# 06_-_CPU_-_HDMI_LVDS.net
KiCad netlist of a schematic drawn in Altium Designer
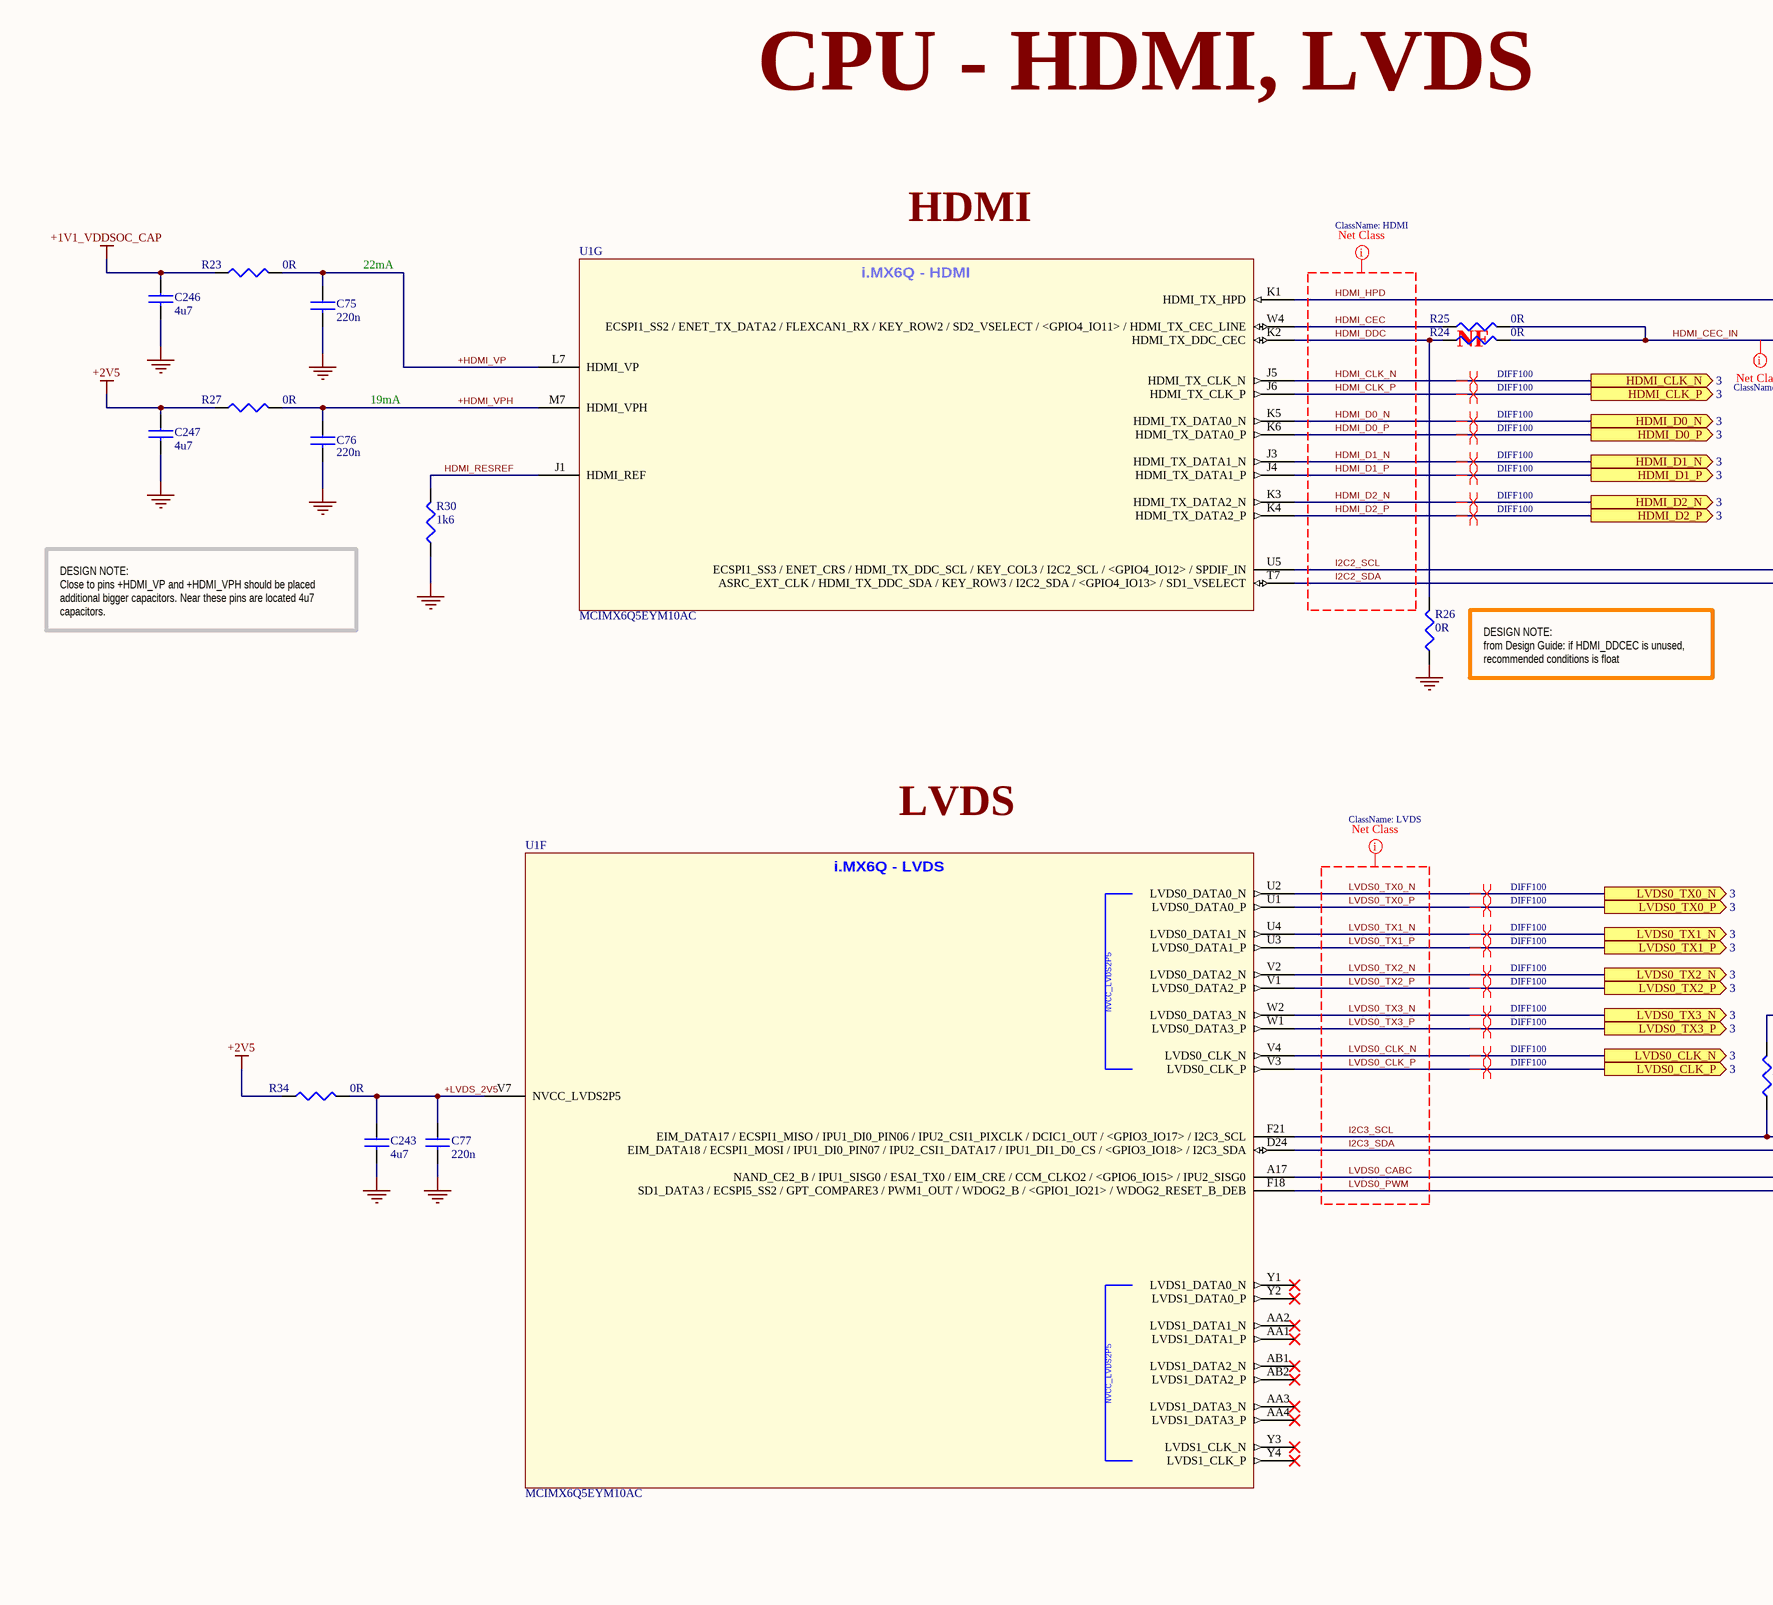
[diagram p0: [06] - CPU - HDMI, LVDS.SchDoc, left]
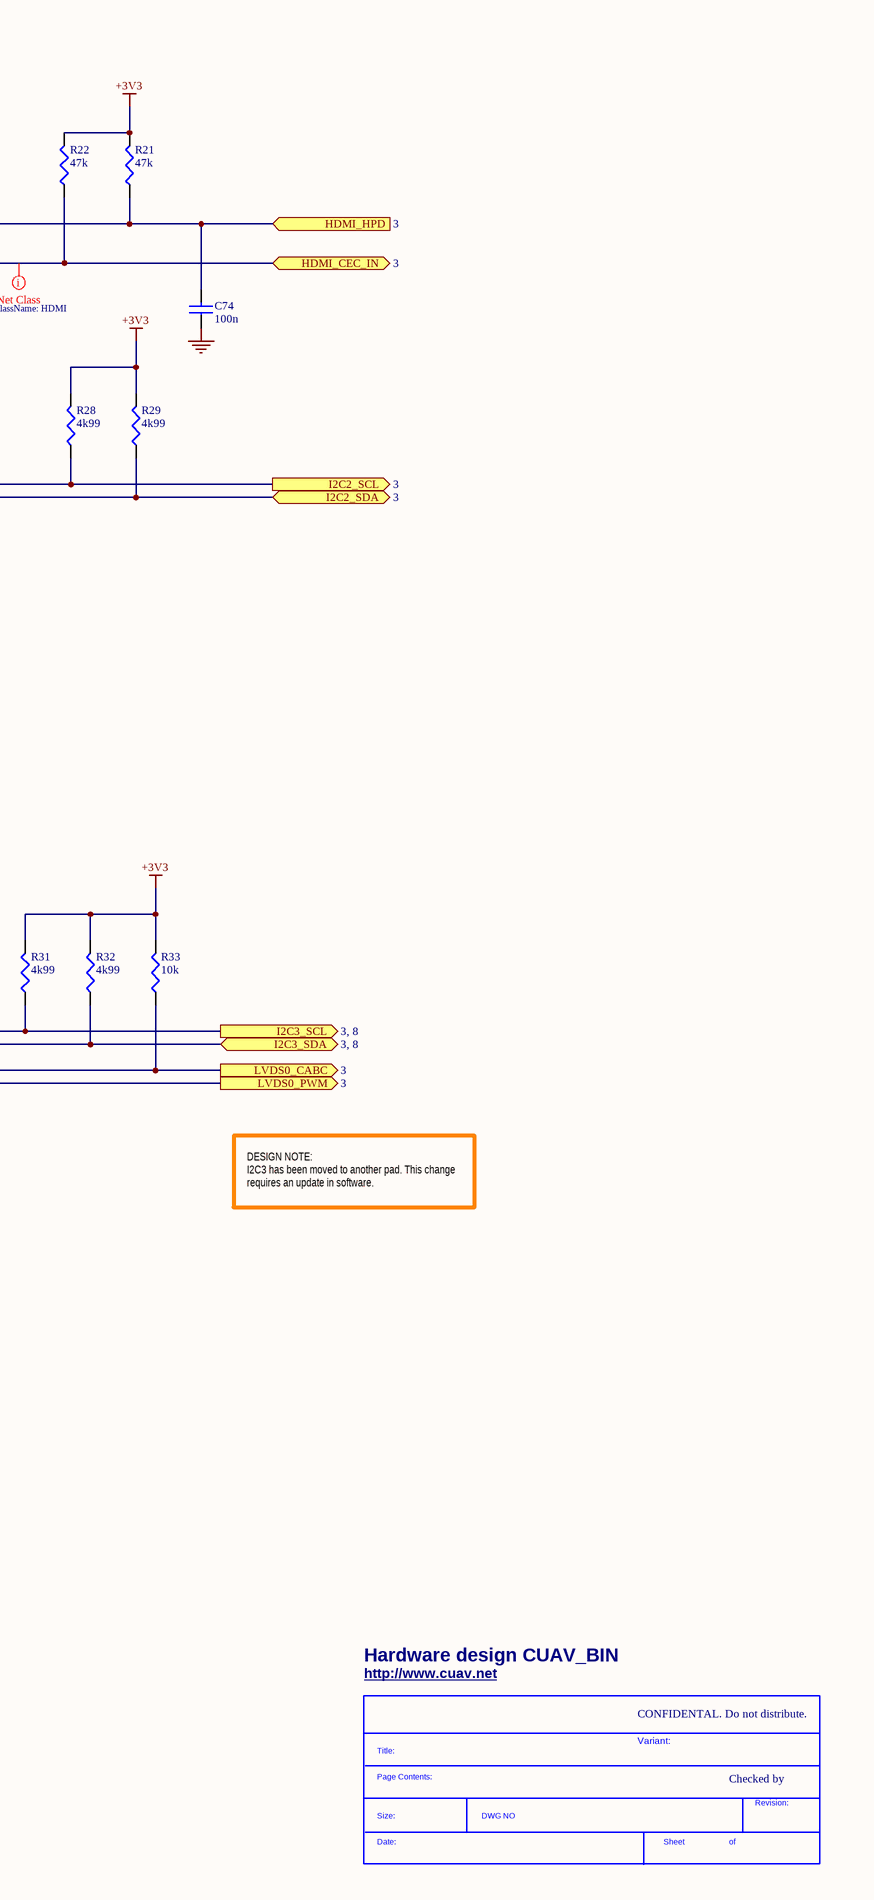
[diagram p1: [06] - CPU - HDMI, LVDS.SchDoc, right]

(export (version "E")
  (design (tool "Eeschema 10.0.6"))
  (components
    (comp (ref "*") (value "SDTitleBlock") (libsource (lib "*") (part "SDTitleBlock")))
    (comp (ref "C74")
      (value "100n")
      (footprint "C0402")
      (description "CAP CER .10UF 50V X5R 10% 0402")
      (fields
        (field (name "MANUFACTURER") "TDK Corporation")
        (field (name "MANUFACTURER PART NUMBER") "C1005X5R1H104K")
      )
      (libsource (lib "Integrated_Library_RF_FEB_2012") (part "C1005X5R1H104K"))
    )
    (comp (ref "C75")
      (value "220n")
      (footprint "C0402")
      (description "CAP CER .22UF 25V X5R 20% 0402")
      (fields
        (field (name "MANUFACTURER") "TDK Corporation")
        (field (name "MANUFACTURER PART NUMBER") "C1005X5R1E224M")
      )
      (libsource (lib "Integrated_Library_RF_FEB_2012") (part "C1005X5R1E224M"))
    )
    (comp (ref "C76")
      (value "220n")
      (footprint "C0402")
      (description "CAP CER .22UF 25V X5R 20% 0402")
      (fields
        (field (name "MANUFACTURER") "TDK Corporation")
        (field (name "MANUFACTURER PART NUMBER") "C1005X5R1E224M")
      )
      (libsource (lib "Integrated_Library_RF_FEB_2012") (part "C1005X5R1E224M"))
    )
    (comp (ref "C77")
      (value "220n")
      (footprint "C0402")
      (description "CAP CER .22UF 25V X5R 20% 0402")
      (fields
        (field (name "MANUFACTURER") "TDK Corporation")
        (field (name "MANUFACTURER PART NUMBER") "C1005X5R1E224M")
      )
      (libsource (lib "Integrated_Library_RF_FEB_2012") (part "C1005X5R1E224M"))
    )
    (comp (ref "C243")
      (value "4u7")
      (footprint "C0402")
      (description "CAP CER 4.7UF 10V 20% X5R 0402")
      (fields
        (field (name "MANUFACTURER") "TDK Corporation")
        (field (name "MANUFACTURER PART NUMBER") "C1005X5R1A475M")
        (field (name ".CHECKED PCB") "RF")
        (field (name ".CHECKED SCH") "RF")
      )
      (libsource (lib "Integrated_Library_RF_FEB_2012") (part "C1005X5R1A475M"))
    )
    (comp (ref "C246")
      (value "4u7")
      (footprint "C0402")
      (description "CAP CER 4.7UF 10V 20% X5R 0402")
      (fields
        (field (name "MANUFACTURER") "TDK Corporation")
        (field (name "MANUFACTURER PART NUMBER") "C1005X5R1A475M")
        (field (name ".CHECKED PCB") "RF")
        (field (name ".CHECKED SCH") "RF")
      )
      (libsource (lib "Integrated_Library_RF_FEB_2012") (part "C1005X5R1A475M"))
    )
    (comp (ref "C247")
      (value "4u7")
      (footprint "C0402")
      (description "CAP CER 4.7UF 10V 20% X5R 0402")
      (fields
        (field (name "MANUFACTURER") "TDK Corporation")
        (field (name "MANUFACTURER PART NUMBER") "C1005X5R1A475M")
        (field (name ".CHECKED PCB") "RF")
        (field (name ".CHECKED SCH") "RF")
      )
      (libsource (lib "Integrated_Library_RF_FEB_2012") (part "C1005X5R1A475M"))
    )
    (comp (ref "R21")
      (value "47k")
      (footprint "R0402")
      (description "RES 47.0K OHM 1/16W 1% 0402 SMD")
      (fields
        (field (name "MANUFACTURER") "Yageo")
        (field (name "MANUFACTURER PART NUMBER") "RC0402FR-0747KL")
      )
      (libsource (lib "Integrated_Library_RF_FEB_2012") (part "RC0402FR-0747KL"))
    )
    (comp (ref "R22")
      (value "47k")
      (footprint "R0402")
      (description "RES 47.0K OHM 1/16W 1% 0402 SMD")
      (fields
        (field (name "MANUFACTURER") "Yageo")
        (field (name "MANUFACTURER PART NUMBER") "RC0402FR-0747KL")
      )
      (libsource (lib "Integrated_Library_RF_FEB_2012") (part "RC0402FR-0747KL"))
    )
    (comp (ref "R23")
      (value "0R")
      (footprint "R0402")
      (description "RES 0.0 OHM 1/16W 0402 SMD")
      (fields
        (field (name "MANUFACTURER") "Yageo")
        (field (name "MANUFACTURER PART NUMBER") "RC0402JR-070RL")
      )
      (libsource (lib "Integrated_Library_RF_FEB_2012") (part "RC0402JR-070RL"))
    )
    (comp (ref "R24")
      (value "0R")
      (footprint "R0402")
      (description "RES 0.0 OHM 1/16W 0402 SMD")
      (fields
        (field (name "MANUFACTURER") "Yageo")
        (field (name "MANUFACTURER PART NUMBER") "RC0402JR-070RL")
      )
      (libsource (lib "Integrated_Library_RF_FEB_2012") (part "RC0402JR-070RL"))
    )
    (comp (ref "R25")
      (value "0R")
      (footprint "R0402")
      (description "RES 0.0 OHM 1/16W 0402 SMD")
      (fields
        (field (name "MANUFACTURER") "Yageo")
        (field (name "MANUFACTURER PART NUMBER") "RC0402JR-070RL")
      )
      (libsource (lib "Integrated_Library_RF_FEB_2012") (part "RC0402JR-070RL"))
    )
    (comp (ref "R26")
      (value "0R")
      (footprint "R0402")
      (description "RES 0.0 OHM 1/16W 0402 SMD")
      (fields
        (field (name "MANUFACTURER") "Yageo")
        (field (name "MANUFACTURER PART NUMBER") "RC0402JR-070RL")
      )
      (libsource (lib "Integrated_Library_RF_FEB_2012") (part "RC0402JR-070RL"))
    )
    (comp (ref "R27")
      (value "0R")
      (footprint "R0402")
      (description "RES 0.0 OHM 1/16W 0402 SMD")
      (fields
        (field (name "MANUFACTURER") "Yageo")
        (field (name "MANUFACTURER PART NUMBER") "RC0402JR-070RL")
      )
      (libsource (lib "Integrated_Library_RF_FEB_2012") (part "RC0402JR-070RL"))
    )
    (comp (ref "R28")
      (value "4k99")
      (footprint "R0402")
      (description "RES TF 4.99K OHM 1% 1/16W 0402")
      (fields
        (field (name "MANUFACTURER") "Stackpole Electronics Inc")
        (field (name "MANUFACTURER PART NUMBER") "RMCF0402FT4K99")
      )
      (libsource (lib "Integrated_Library_RF_FEB_2012") (part "RMCF0402FT4K99"))
    )
    (comp (ref "R29")
      (value "4k99")
      (footprint "R0402")
      (description "RES TF 4.99K OHM 1% 1/16W 0402")
      (fields
        (field (name "MANUFACTURER") "Stackpole Electronics Inc")
        (field (name "MANUFACTURER PART NUMBER") "RMCF0402FT4K99")
      )
      (libsource (lib "Integrated_Library_RF_FEB_2012") (part "RMCF0402FT4K99"))
    )
    (comp (ref "R30")
      (value "1k6")
      (footprint "R0402")
      (description "RES 1.6K OHM 1/10W 1% 0402 SMD")
      (fields
        (field (name "MANUFACTURER") "Panasonic Electronic Components")
        (field (name "MANUFACTURER PART NUMBER") "ERJ-2RKF1601X")
        (field (name ".CREATOR") "MM")
        (field (name ".CHECKED PCB") "RF, used by MM")
        (field (name ".CHECKED SCH") "MM, checked by RF")
      )
      (libsource (lib "Schlib_RF") (part "ERJ-2RKF1601X"))
    )
    (comp (ref "R31")
      (value "4k99")
      (footprint "R0402")
      (description "RES TF 4.99K OHM 1% 1/16W 0402")
      (fields
        (field (name "MANUFACTURER") "Stackpole Electronics Inc")
        (field (name "MANUFACTURER PART NUMBER") "RMCF0402FT4K99")
      )
      (libsource (lib "Integrated_Library_RF_FEB_2012") (part "RMCF0402FT4K99"))
    )
    (comp (ref "R32")
      (value "4k99")
      (footprint "R0402")
      (description "RES TF 4.99K OHM 1% 1/16W 0402")
      (fields
        (field (name "MANUFACTURER") "Stackpole Electronics Inc")
        (field (name "MANUFACTURER PART NUMBER") "RMCF0402FT4K99")
      )
      (libsource (lib "Integrated_Library_RF_FEB_2012") (part "RMCF0402FT4K99"))
    )
    (comp (ref "R33")
      (value "10k")
      (footprint "R0402")
      (description "RES 10.0K OHM 1/16W 1% 0402 SMD")
      (fields
        (field (name "MANUFACTURER") "Yageo")
        (field (name "MANUFACTURER PART NUMBER") "RC0402FR-0710KL")
      )
      (libsource (lib "Integrated_Library_RF_FEB_2012") (part "RC0402FR-0710KL"))
    )
    (comp (ref "R34")
      (value "0R")
      (footprint "R0402")
      (description "RES 0.0 OHM 1/16W 0402 SMD")
      (fields
        (field (name "MANUFACTURER") "Yageo")
        (field (name "MANUFACTURER PART NUMBER") "RC0402JR-070RL")
      )
      (libsource (lib "Integrated_Library_RF_FEB_2012") (part "RC0402JR-070RL"))
    )
    (comp (ref "U1")
      (value "MCIMX6Q5EYM10AC")
      (footprint "PBGA624")
      (description "IC MCU 32BIT ARM QUAD 624FCBGA")
      (fields
        (field (name "MANUFACTURER") "Freescale Semiconductor")
        (field (name ".CREATOR") "MM")
        (field (name ".CHECKED PCB") "MM, checked by RF")
        (field (name ".CHECKED SCH") "MM")
      )
      (libsource (lib "Schlib_RF") (part "MCIMX6Q5EYM10AC"))
    )
  )
  (nets
    (net (code "1") (name "+1V1_VDDSOC_CAP") (class "Default")
      (node (ref "C246") (pin "1") (pinfunction "1_1") (pintype "passive"))
      (node (ref "R23") (pin "1") (pinfunction "1_1") (pintype "passive"))
    )
    (net (code "2") (name "+2V5") (class "Default")
      (node (ref "C247") (pin "1") (pinfunction "1_1") (pintype "passive"))
      (node (ref "R27") (pin "1") (pinfunction "1_1") (pintype "passive"))
      (node (ref "R34") (pin "1") (pinfunction "1_1") (pintype "passive"))
    )
    (net (code "3") (name "+3V3") (class "Default")
      (node (ref "R21") (pin "2") (pinfunction "2_2") (pintype "passive"))
      (node (ref "R22") (pin "2") (pinfunction "2_2") (pintype "passive"))
      (node (ref "R28") (pin "2") (pinfunction "2_2") (pintype "passive"))
      (node (ref "R29") (pin "2") (pinfunction "2_2") (pintype "passive"))
      (node (ref "R31") (pin "2") (pinfunction "2_2") (pintype "passive"))
      (node (ref "R32") (pin "2") (pinfunction "2_2") (pintype "passive"))
      (node (ref "R33") (pin "2") (pinfunction "2_2") (pintype "passive"))
    )
    (net (code "4") (name "/+HDMI_VP") (class "Default")
      (node (ref "C75") (pin "1") (pinfunction "1_1") (pintype "passive"))
      (node (ref "R23") (pin "2") (pinfunction "2_2") (pintype "passive"))
      (node (ref "U1") (pin "L7") (pinfunction "HDMI_VP_L7") (pintype "power_in"))
    )
    (net (code "5") (name "/+HDMI_VPH") (class "Default")
      (node (ref "C76") (pin "1") (pinfunction "1_1") (pintype "passive"))
      (node (ref "R27") (pin "2") (pinfunction "2_2") (pintype "passive"))
      (node (ref "U1") (pin "M7") (pinfunction "HDMI_VPH_M7") (pintype "power_in"))
    )
    (net (code "6") (name "/+LVDS_2V5") (class "Default")
      (node (ref "C243") (pin "1") (pinfunction "1_1") (pintype "passive"))
      (node (ref "C77") (pin "1") (pinfunction "1_1") (pintype "passive"))
      (node (ref "R34") (pin "2") (pinfunction "2_2") (pintype "passive"))
      (node (ref "U1") (pin "V7") (pinfunction "NVCC_LVDS2P5_V7") (pintype "power_in"))
    )
    (net (code "7") (name "/HDMI_CEC") (class "Default")
      (node (ref "R25") (pin "1") (pinfunction "1_1") (pintype "passive"))
      (node (ref "U1") (pin "W4") (pinfunction "ECSPI1_SS2_/_ENET_TX_DATA2_/_FLEXCAN1_RX_/_KEY_ROW2_/_SD2_VSELECT_/_<GPIO4_IO11>_/_HDMI_TX_CEC_LINE_W4") (pintype "bidirectional"))
    )
    (net (code "8") (name "/HDMI_CEC_IN") (class "Default")
      (node (ref "R22") (pin "1") (pinfunction "1_1") (pintype "passive"))
      (node (ref "R24") (pin "2") (pinfunction "2_2") (pintype "passive"))
      (node (ref "R25") (pin "2") (pinfunction "2_2") (pintype "passive"))
    )
    (net (code "9") (name "/HDMI_CLK_N") (class "Default")
      (node (ref "U1") (pin "J5") (pinfunction "HDMI_TX_CLK_N_J5") (pintype "output"))
    )
    (net (code "10") (name "/HDMI_CLK_P") (class "Default")
      (node (ref "U1") (pin "J6") (pinfunction "HDMI_TX_CLK_P_J6") (pintype "output"))
    )
    (net (code "11") (name "/HDMI_D0_N") (class "Default")
      (node (ref "U1") (pin "K5") (pinfunction "HDMI_TX_DATA0_N_K5") (pintype "output"))
    )
    (net (code "12") (name "/HDMI_D0_P") (class "Default")
      (node (ref "U1") (pin "K6") (pinfunction "HDMI_TX_DATA0_P_K6") (pintype "output"))
    )
    (net (code "13") (name "/HDMI_D1_N") (class "Default")
      (node (ref "U1") (pin "J3") (pinfunction "HDMI_TX_DATA1_N_J3") (pintype "output"))
    )
    (net (code "14") (name "/HDMI_D1_P") (class "Default")
      (node (ref "U1") (pin "J4") (pinfunction "HDMI_TX_DATA1_P_J4") (pintype "output"))
    )
    (net (code "15") (name "/HDMI_D2_N") (class "Default")
      (node (ref "U1") (pin "K3") (pinfunction "HDMI_TX_DATA2_N_K3") (pintype "output"))
    )
    (net (code "16") (name "/HDMI_D2_P") (class "Default")
      (node (ref "U1") (pin "K4") (pinfunction "HDMI_TX_DATA2_P_K4") (pintype "output"))
    )
    (net (code "17") (name "/HDMI_DDC") (class "Default")
      (node (ref "R24") (pin "1") (pinfunction "1_1") (pintype "passive"))
      (node (ref "R26") (pin "2") (pinfunction "2_2") (pintype "passive"))
      (node (ref "U1") (pin "K2") (pinfunction "HDMI_TX_DDC_CEC_K2") (pintype "bidirectional"))
    )
    (net (code "18") (name "/HDMI_HPD") (class "Default")
      (node (ref "C74") (pin "2") (pinfunction "2_2") (pintype "passive"))
      (node (ref "R21") (pin "1") (pinfunction "1_1") (pintype "passive"))
      (node (ref "U1") (pin "K1") (pinfunction "HDMI_TX_HPD_K1") (pintype "input"))
    )
    (net (code "19") (name "/HDMI_RESREF") (class "Default")
      (node (ref "R30") (pin "2") (pinfunction "2_2") (pintype "passive"))
      (node (ref "U1") (pin "J1") (pinfunction "HDMI_REF_J1") (pintype "passive"))
    )
    (net (code "20") (name "/I2C2_SCL") (class "Default")
      (node (ref "R28") (pin "1") (pinfunction "1_1") (pintype "passive"))
      (node (ref "U1") (pin "U5") (pinfunction "ECSPI1_SS3_/_ENET_CRS_/_HDMI_TX_DDC_SCL_/_KEY_COL3_/_I2C2_SCL_/_<GPIO4_IO12>_/_SPDIF_IN_U5") (pintype "passive"))
    )
    (net (code "21") (name "/I2C2_SDA") (class "Default")
      (node (ref "R29") (pin "1") (pinfunction "1_1") (pintype "passive"))
      (node (ref "U1") (pin "T7") (pinfunction "ASRC_EXT_CLK_/_HDMI_TX_DDC_SDA_/_KEY_ROW3_/_I2C2_SDA_/_<GPIO4_IO13>_/_SD1_VSELECT_T7") (pintype "bidirectional"))
    )
    (net (code "22") (name "/I2C3_SCL") (class "Default")
      (node (ref "R31") (pin "1") (pinfunction "1_1") (pintype "passive"))
      (node (ref "U1") (pin "F21") (pinfunction "EIM_DATA17_/_ECSPI1_MISO_/_IPU1_DI0_PIN06_/_IPU2_CSI1_PIXCLK_/_DCIC1_OUT_/_<GPIO3_IO17>_/_I2C3_SCL_F21") (pintype "passive"))
    )
    (net (code "23") (name "/I2C3_SDA") (class "Default")
      (node (ref "R32") (pin "1") (pinfunction "1_1") (pintype "passive"))
      (node (ref "U1") (pin "D24") (pinfunction "EIM_DATA18_/_ECSPI1_MOSI_/_IPU1_DI0_PIN07_/_IPU2_CSI1_DATA17_/_IPU1_DI1_D0_CS_/_<GPIO3_IO18>_/_I2C3_SDA_D24") (pintype "bidirectional"))
    )
    (net (code "24") (name "/LVDS0_CABC") (class "Default")
      (node (ref "R33") (pin "1") (pinfunction "1_1") (pintype "passive"))
      (node (ref "U1") (pin "A17") (pinfunction "NAND_CE2_B_/_IPU1_SISG0_/_ESAI_TX0_/_EIM_CRE_/_CCM_CLKO2_/_<GPIO6_IO15>_/_IPU2_SISG0_A17") (pintype "passive"))
    )
    (net (code "25") (name "/LVDS0_CLK_N") (class "Default")
      (node (ref "U1") (pin "V4") (pinfunction "LVDS0_CLK_N_V4") (pintype "output"))
    )
    (net (code "26") (name "/LVDS0_CLK_P") (class "Default")
      (node (ref "U1") (pin "V3") (pinfunction "LVDS0_CLK_P_V3") (pintype "output"))
    )
    (net (code "27") (name "/LVDS0_PWM") (class "Default")
      (node (ref "U1") (pin "F18") (pinfunction "SD1_DATA3_/_ECSPI5_SS2_/_GPT_COMPARE3_/_PWM1_OUT_/_WDOG2_B_/_<GPIO1_IO21>_/_WDOG2_RESET_B_DEB_F18") (pintype "passive"))
    )
    (net (code "28") (name "/LVDS0_TX0_N") (class "Default")
      (node (ref "U1") (pin "U2") (pinfunction "LVDS0_DATA0_N_U2") (pintype "output"))
    )
    (net (code "29") (name "/LVDS0_TX0_P") (class "Default")
      (node (ref "U1") (pin "U1") (pinfunction "LVDS0_DATA0_P_U1") (pintype "output"))
    )
    (net (code "30") (name "/LVDS0_TX1_N") (class "Default")
      (node (ref "U1") (pin "U4") (pinfunction "LVDS0_DATA1_N_U4") (pintype "output"))
    )
    (net (code "31") (name "/LVDS0_TX1_P") (class "Default")
      (node (ref "U1") (pin "U3") (pinfunction "LVDS0_DATA1_P_U3") (pintype "output"))
    )
    (net (code "32") (name "/LVDS0_TX2_N") (class "Default")
      (node (ref "U1") (pin "V2") (pinfunction "LVDS0_DATA2_N_V2") (pintype "output"))
    )
    (net (code "33") (name "/LVDS0_TX2_P") (class "Default")
      (node (ref "U1") (pin "V1") (pinfunction "LVDS0_DATA2_P_V1") (pintype "output"))
    )
    (net (code "34") (name "/LVDS0_TX3_N") (class "Default")
      (node (ref "U1") (pin "W2") (pinfunction "LVDS0_DATA3_N_W2") (pintype "output"))
    )
    (net (code "35") (name "/LVDS0_TX3_P") (class "Default")
      (node (ref "U1") (pin "W1") (pinfunction "LVDS0_DATA3_P_W1") (pintype "output"))
    )
    (net (code "36") (name "GND") (class "Default")
      (node (ref "C243") (pin "2") (pinfunction "2_2") (pintype "passive"))
      (node (ref "C246") (pin "2") (pinfunction "2_2") (pintype "passive"))
      (node (ref "C247") (pin "2") (pinfunction "2_2") (pintype "passive"))
      (node (ref "C74") (pin "1") (pinfunction "1_1") (pintype "passive"))
      (node (ref "C75") (pin "2") (pinfunction "2_2") (pintype "passive"))
      (node (ref "C76") (pin "2") (pinfunction "2_2") (pintype "passive"))
      (node (ref "C77") (pin "2") (pinfunction "2_2") (pintype "passive"))
      (node (ref "R26") (pin "1") (pinfunction "1_1") (pintype "passive"))
      (node (ref "R30") (pin "1") (pinfunction "1_1") (pintype "passive"))
    )
    (net (code "37") (name "unconnected-(U1F-LVDS1_CLK_N-PadY3)") (class "Default")
      (node (ref "U1") (pin "Y3") (pinfunction "LVDS1_CLK_N_Y3") (pintype "output+no_connect"))
    )
    (net (code "38") (name "unconnected-(U1F-LVDS1_CLK_P-PadY4)") (class "Default")
      (node (ref "U1") (pin "Y4") (pinfunction "LVDS1_CLK_P_Y4") (pintype "output+no_connect"))
    )
    (net (code "39") (name "unconnected-(U1F-LVDS1_DATA0_N-PadY1)") (class "Default")
      (node (ref "U1") (pin "Y1") (pinfunction "LVDS1_DATA0_N_Y1") (pintype "output+no_connect"))
    )
    (net (code "40") (name "unconnected-(U1F-LVDS1_DATA0_P-PadY2)") (class "Default")
      (node (ref "U1") (pin "Y2") (pinfunction "LVDS1_DATA0_P_Y2") (pintype "output+no_connect"))
    )
    (net (code "41") (name "unconnected-(U1F-LVDS1_DATA1_N-PadAA2)") (class "Default")
      (node (ref "U1") (pin "AA2") (pinfunction "LVDS1_DATA1_N_AA2") (pintype "output+no_connect"))
    )
    (net (code "42") (name "unconnected-(U1F-LVDS1_DATA1_P-PadAA1)") (class "Default")
      (node (ref "U1") (pin "AA1") (pinfunction "LVDS1_DATA1_P_AA1") (pintype "output+no_connect"))
    )
    (net (code "43") (name "unconnected-(U1F-LVDS1_DATA2_N-PadAB1)") (class "Default")
      (node (ref "U1") (pin "AB1") (pinfunction "LVDS1_DATA2_N_AB1") (pintype "output+no_connect"))
    )
    (net (code "44") (name "unconnected-(U1F-LVDS1_DATA2_P-PadAB2)") (class "Default")
      (node (ref "U1") (pin "AB2") (pinfunction "LVDS1_DATA2_P_AB2") (pintype "output+no_connect"))
    )
    (net (code "45") (name "unconnected-(U1F-LVDS1_DATA3_N-PadAA3)") (class "Default")
      (node (ref "U1") (pin "AA3") (pinfunction "LVDS1_DATA3_N_AA3") (pintype "output+no_connect"))
    )
    (net (code "46") (name "unconnected-(U1F-LVDS1_DATA3_P-PadAA4)") (class "Default")
      (node (ref "U1") (pin "AA4") (pinfunction "LVDS1_DATA3_P_AA4") (pintype "output+no_connect"))
    )
  )
)
